# regulated_sensorTHV18.net
KiCad netlist of a schematic drawn in EAGLE
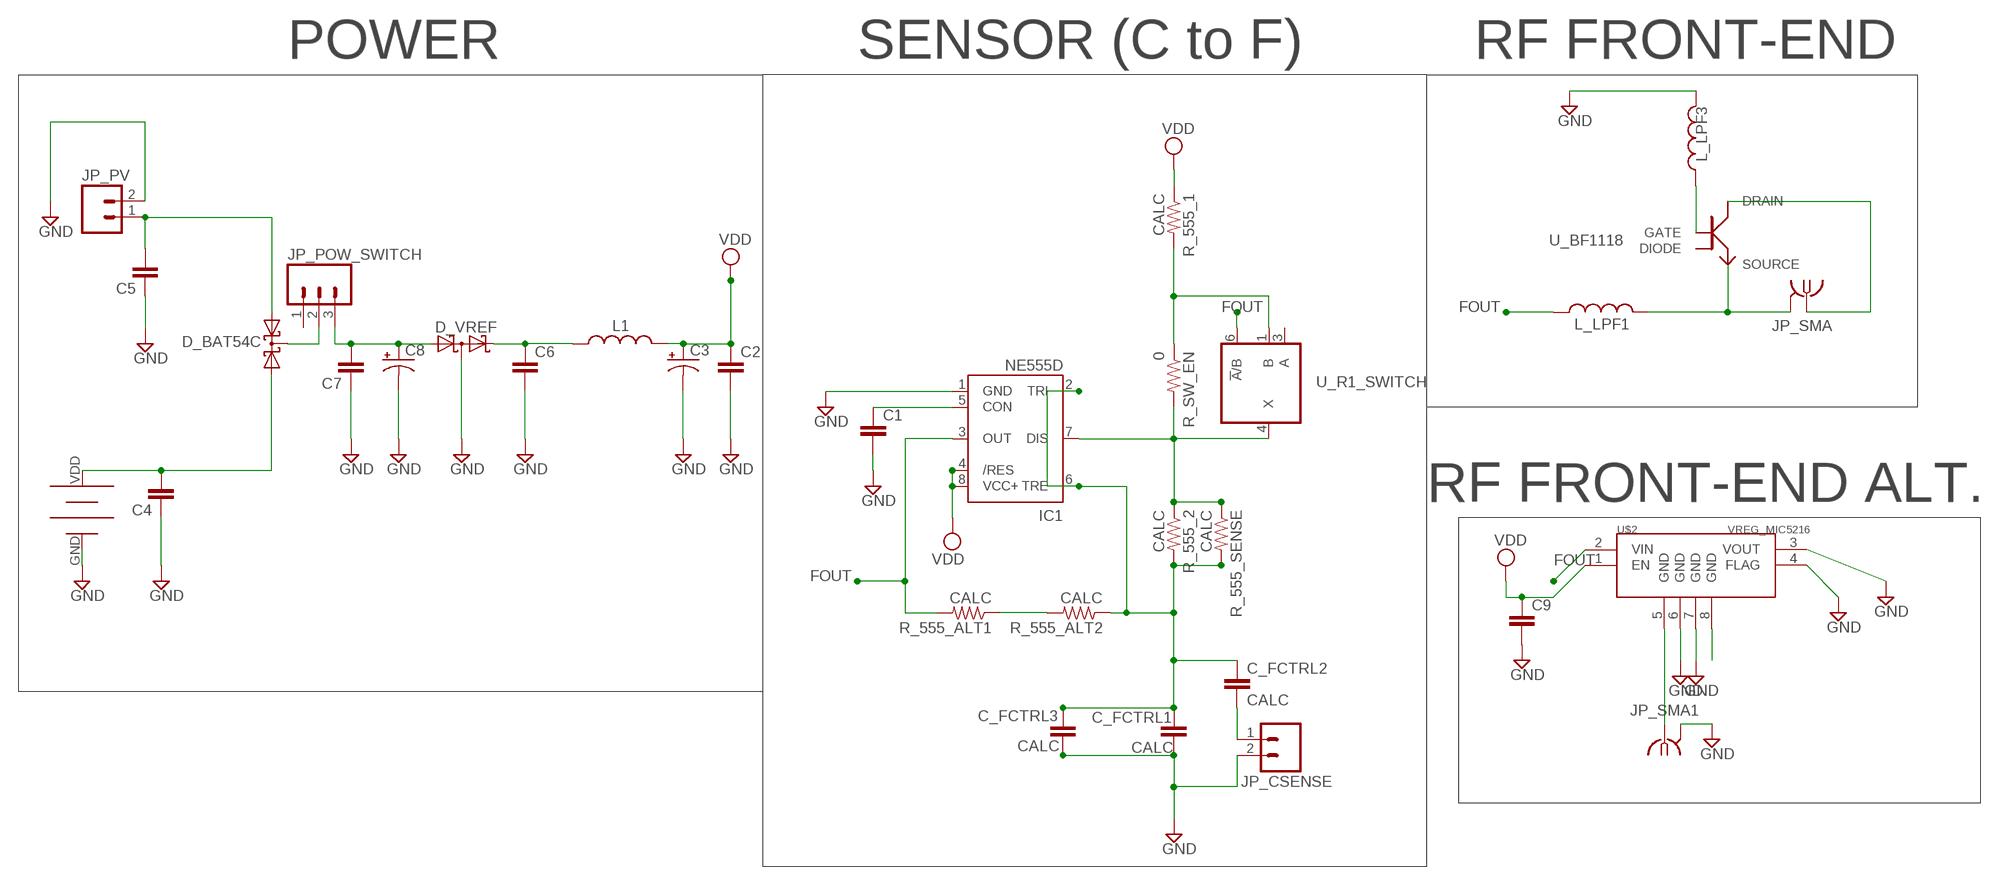
[diagram p0: schematic, sheet 1]

(export (version "E")
  (design (tool "Eeschema 10.0.6"))
  (components
    (comp (ref "C1")
      (value "CAP0603-CAP")
      (footprint "eagle-import:0603-CAP")
      (libsource (lib "eagle-import") (part "CAP0603-CAP"))
    )
    (comp (ref "C2")
      (value "CAP0603-CAP")
      (footprint "eagle-import:0603-CAP")
      (libsource (lib "eagle-import") (part "CAP0603-CAP"))
    )
    (comp (ref "C3")
      (value "CAP_POL1206")
      (footprint "eagle-import:EIA3216")
      (libsource (lib "eagle-import") (part "CAP_POL1206"))
    )
    (comp (ref "C4")
      (value "CAP0603-CAP")
      (footprint "eagle-import:0603-CAP")
      (libsource (lib "eagle-import") (part "CAP0603-CAP"))
    )
    (comp (ref "C5")
      (value "CAP0603-CAP")
      (footprint "eagle-import:0603-CAP")
      (libsource (lib "eagle-import") (part "CAP0603-CAP"))
    )
    (comp (ref "C6")
      (value "CAP0603-CAP")
      (footprint "eagle-import:0603-CAP")
      (libsource (lib "eagle-import") (part "CAP0603-CAP"))
    )
    (comp (ref "C7")
      (value "CAP0603-CAP")
      (footprint "eagle-import:0603-CAP")
      (libsource (lib "eagle-import") (part "CAP0603-CAP"))
    )
    (comp (ref "C8")
      (value "CAP_POL1206")
      (footprint "eagle-import:EIA3216")
      (libsource (lib "eagle-import") (part "CAP_POL1206"))
    )
    (comp (ref "C9")
      (value "CAP0603-CAP")
      (footprint "eagle-import:0603-CAP")
      (libsource (lib "eagle-import") (part "CAP0603-CAP"))
    )
    (comp (ref "C_FCTRL1")
      (value "CALC")
      (footprint "eagle-import:0603-CAP")
      (libsource (lib "eagle-import") (part "CAP0603-CAP"))
    )
    (comp (ref "C_FCTRL2")
      (value "CALC")
      (footprint "eagle-import:0603-CAP")
      (libsource (lib "eagle-import") (part "CAP0603-CAP"))
    )
    (comp (ref "C_FCTRL3")
      (value "CALC")
      (footprint "eagle-import:0603-CAP")
      (libsource (lib "eagle-import") (part "CAP0603-CAP"))
    )
    (comp (ref "D_BAT54C")
      (value "BAT54C")
      (footprint "eagle-import:SOT23")
      (libsource (lib "eagle-import") (part "BAT54C"))
    )
    (comp (ref "D_VREF")
      (value "BAT54S")
      (footprint "eagle-import:SOT23")
      (libsource (lib "eagle-import") (part "BAT54S"))
    )
    (comp (ref "IC1")
      (value "NE555D")
      (footprint "eagle-import:SO08")
      (libsource (lib "eagle-import") (part "NE555D"))
    )
    (comp (ref "JP_CSENSE")
      (value "M02LOCK")
      (footprint "eagle-import:1X02_LOCK")
      (libsource (lib "eagle-import") (part "M02LOCK"))
    )
    (comp (ref "JP_POW_SWITCH")
      (value "M03LOCK")
      (footprint "eagle-import:1X03_LOCK")
      (libsource (lib "eagle-import") (part "M03LOCK"))
    )
    (comp (ref "JP_PV")
      (value "M02LOCK")
      (footprint "eagle-import:1X02_LOCK")
      (libsource (lib "eagle-import") (part "M02LOCK"))
    )
    (comp (ref "JP_SMA")
      (value "SMA-142-0701-881/886")
      (footprint "eagle-import:J502-ND-142-0701-881_886")
      (fields (field (name "MF") "JOHNSON COMPONENTS") (field (name "MPN") "142-0701-881"))
      (libsource (lib "eagle-import") (part "SMA-142-0701-881/886"))
    )
    (comp (ref "JP_SMA1")
      (value "SMA-142-0701-881/886")
      (footprint "eagle-import:J502-ND-142-0701-881_886")
      (fields (field (name "MF") "JOHNSON COMPONENTS") (field (name "MPN") "142-0701-881"))
      (libsource (lib "eagle-import") (part "SMA-142-0701-881/886"))
    )
    (comp (ref "L1")
      (value "INDUCTOR0603")
      (footprint "eagle-import:0603")
      (libsource (lib "eagle-import") (part "INDUCTOR0603"))
    )
    (comp (ref "L_LPF1")
      (value "INDUCTOR0603")
      (footprint "eagle-import:0603")
      (libsource (lib "eagle-import") (part "INDUCTOR0603"))
    )
    (comp (ref "L_LPF3")
      (value "INDUCTOR0603")
      (footprint "eagle-import:0603")
      (libsource (lib "eagle-import") (part "INDUCTOR0603"))
    )
    (comp (ref "R_555_1")
      (value "CALC")
      (footprint "eagle-import:0805")
      (libsource (lib "eagle-import") (part "RESISTOR0805-RES"))
    )
    (comp (ref "R_555_2")
      (value "CALC")
      (footprint "eagle-import:0603-RES")
      (libsource (lib "eagle-import") (part "RESISTOR0603-RES"))
    )
    (comp (ref "R_555_ALT1")
      (value "CALC")
      (footprint "eagle-import:0603-RES")
      (libsource (lib "eagle-import") (part "RESISTOR0603-RES"))
    )
    (comp (ref "R_555_ALT2")
      (value "CALC")
      (footprint "eagle-import:0603-RES")
      (libsource (lib "eagle-import") (part "RESISTOR0603-RES"))
    )
    (comp (ref "R_555_SENSE")
      (value "CALC")
      (footprint "eagle-import:0603-RES")
      (libsource (lib "eagle-import") (part "RESISTOR0603-RES"))
    )
    (comp (ref "R_SW_EN")
      (value "0")
      (footprint "eagle-import:0805")
      (libsource (lib "eagle-import") (part "RESISTOR0805-RES"))
    )
    (comp (ref "U$1")
      (value "BATTERY_AAA_EAGLE_PLASTIC_DEVICES_DOUBLE")
      (footprint "eagle-import:BATTERY-AAA-50MM-DOUBLE")
      (libsource (lib "eagle-import") (part "BATTERY_AAA_EAGLE_PLASTIC_DEVICES_DOUBLE"))
    )
    (comp (ref "U$2")
      (value "VREG_MIC5216")
      (footprint "eagle-import:MSOP8")
      (libsource (lib "eagle-import") (part "VREG_MIC5216"))
    )
    (comp (ref "U_BF1118")
      (value "BF1118SOT343R_NXP")
      (footprint "eagle-import:SOT343R")
      (libsource (lib "eagle-import") (part "BF1118SOT343R_NXP"))
    )
    (comp (ref "U_R1_SWITCH")
      (value "741G3157DCKR")
      (footprint "eagle-import:DCK_R-PDSO-G6")
      (libsource (lib "eagle-import") (part "741G3157DCKR"))
    )
  )
  (nets
    (net (code "1") (name "/FOUT") (class "Default")
      (node (ref "IC1") (pin "3") (pinfunction "OUT_3") (pintype "output"))
      (node (ref "L_LPF1") (pin "1") (pinfunction "1_1") (pintype "passive"))
      (node (ref "R_555_ALT1") (pin "2") (pinfunction "2_2") (pintype "passive"))
      (node (ref "U$2") (pin "2") (pinfunction "VIN_2") (pintype "bidirectional"))
      (node (ref "U_R1_SWITCH") (pin "6") (pinfunction "~{A}/B_6") (pintype "input"))
    )
    (net (code "2") (name "GND") (class "Default")
      (node (ref "C1") (pin "2") (pinfunction "2_2") (pintype "passive"))
      (node (ref "C2") (pin "2") (pinfunction "2_2") (pintype "passive"))
      (node (ref "C3") (pin "C") (pinfunction "-_C") (pintype "passive"))
      (node (ref "C4") (pin "1") (pinfunction "1_1") (pintype "passive"))
      (node (ref "C5") (pin "1") (pinfunction "1_1") (pintype "passive"))
      (node (ref "C6") (pin "2") (pinfunction "2_2") (pintype "passive"))
      (node (ref "C7") (pin "1") (pinfunction "1_1") (pintype "passive"))
      (node (ref "C8") (pin "C") (pinfunction "-_C") (pintype "passive"))
      (node (ref "C9") (pin "2") (pinfunction "2_2") (pintype "passive"))
      (node (ref "C_FCTRL1") (pin "2") (pinfunction "2_2") (pintype "passive"))
      (node (ref "C_FCTRL3") (pin "2") (pinfunction "2_2") (pintype "passive"))
      (node (ref "D_VREF") (pin "3") (pinfunction "C1A2_3") (pintype "passive"))
      (node (ref "IC1") (pin "1") (pinfunction "GND_1") (pintype "power_in"))
      (node (ref "JP_CSENSE") (pin "2") (pinfunction "2_2") (pintype "passive"))
      (node (ref "JP_PV") (pin "2") (pinfunction "2_2") (pintype "passive"))
      (node (ref "JP_SMA1") (pin "G@1") (pinfunction "2_G@1") (pintype "passive"))
      (node (ref "JP_SMA1") (pin "G@2") (pinfunction "2_G@2") (pintype "passive"))
      (node (ref "JP_SMA1") (pin "G@3") (pinfunction "2_G@3") (pintype "passive"))
      (node (ref "JP_SMA1") (pin "G@4") (pinfunction "2_G@4") (pintype "passive"))
      (node (ref "L_LPF3") (pin "2") (pinfunction "2_2") (pintype "passive"))
      (node (ref "U$1") (pin "GND") (pinfunction "GND_GND") (pintype "bidirectional"))
      (node (ref "U$2") (pin "3") (pinfunction "VOUT_3") (pintype "bidirectional"))
      (node (ref "U$2") (pin "4") (pinfunction "FLAG_4") (pintype "bidirectional"))
      (node (ref "U$2") (pin "6") (pinfunction "GND_6") (pintype "bidirectional"))
      (node (ref "U$2") (pin "7") (pinfunction "GND_7") (pintype "bidirectional"))
    )
    (net (code "3") (name "Net-(C8-+)") (class "Default")
      (node (ref "C7") (pin "2") (pinfunction "2_2") (pintype "passive"))
      (node (ref "C8") (pin "A") (pinfunction "+_A") (pintype "passive"))
      (node (ref "D_VREF") (pin "1") (pinfunction "A1_1") (pintype "passive"))
      (node (ref "JP_POW_SWITCH") (pin "3") (pinfunction "3_3") (pintype "passive"))
    )
    (net (code "4") (name "Net-(C_FCTRL2-Pad2)") (class "Default")
      (node (ref "C_FCTRL2") (pin "2") (pinfunction "2_2") (pintype "passive"))
      (node (ref "JP_CSENSE") (pin "1") (pinfunction "1_1") (pintype "passive"))
    )
    (net (code "5") (name "Net-(D_BAT54C-A1)") (class "Default")
      (node (ref "C5") (pin "2") (pinfunction "2_2") (pintype "passive"))
      (node (ref "D_BAT54C") (pin "1") (pinfunction "A1_1") (pintype "passive"))
      (node (ref "JP_PV") (pin "1") (pinfunction "1_1") (pintype "passive"))
    )
    (net (code "6") (name "Net-(D_BAT54C-A2)") (class "Default")
      (node (ref "C4") (pin "2") (pinfunction "2_2") (pintype "passive"))
      (node (ref "D_BAT54C") (pin "2") (pinfunction "A2_2") (pintype "passive"))
      (node (ref "U$1") (pin "VDD") (pinfunction "VDD_VDD") (pintype "bidirectional"))
    )
    (net (code "7") (name "Net-(D_BAT54C-CC)") (class "Default")
      (node (ref "D_BAT54C") (pin "3") (pinfunction "CC_3") (pintype "passive"))
      (node (ref "JP_POW_SWITCH") (pin "2") (pinfunction "2_2") (pintype "passive"))
    )
    (net (code "8") (name "Net-(D_VREF-C2)") (class "Default")
      (node (ref "C6") (pin "1") (pinfunction "1_1") (pintype "passive"))
      (node (ref "D_VREF") (pin "2") (pinfunction "C2_2") (pintype "passive"))
      (node (ref "L1") (pin "1") (pinfunction "1_1") (pintype "passive"))
    )
    (net (code "9") (name "Net-(IC1-CON)") (class "Default")
      (node (ref "C1") (pin "1") (pinfunction "1_1") (pintype "passive"))
      (node (ref "IC1") (pin "5") (pinfunction "CON_5") (pintype "input"))
    )
    (net (code "10") (name "Net-(IC1-DIS)") (class "Default")
      (node (ref "IC1") (pin "7") (pinfunction "DIS_7") (pintype "input"))
      (node (ref "R_555_2") (pin "1") (pinfunction "1_1") (pintype "passive"))
      (node (ref "R_555_SENSE") (pin "1") (pinfunction "1_1") (pintype "passive"))
      (node (ref "R_SW_EN") (pin "2") (pinfunction "2_2") (pintype "passive"))
      (node (ref "U_R1_SWITCH") (pin "4") (pinfunction "X_4") (pintype "bidirectional"))
    )
    (net (code "11") (name "Net-(IC1-TRE)") (class "Default")
      (node (ref "C_FCTRL1") (pin "1") (pinfunction "1_1") (pintype "passive"))
      (node (ref "C_FCTRL2") (pin "1") (pinfunction "1_1") (pintype "passive"))
      (node (ref "C_FCTRL3") (pin "1") (pinfunction "1_1") (pintype "passive"))
      (node (ref "IC1") (pin "2") (pinfunction "TRI_2") (pintype "input"))
      (node (ref "IC1") (pin "6") (pinfunction "TRE_6") (pintype "input"))
      (node (ref "R_555_2") (pin "2") (pinfunction "2_2") (pintype "passive"))
      (node (ref "R_555_ALT2") (pin "1") (pinfunction "1_1") (pintype "passive"))
      (node (ref "R_555_SENSE") (pin "2") (pinfunction "2_2") (pintype "passive"))
    )
    (net (code "12") (name "Net-(JP_SMA1-Pad1)") (class "Default")
      (node (ref "JP_SMA1") (pin "1") (pinfunction "1_1") (pintype "passive"))
      (node (ref "U$2") (pin "5") (pinfunction "GND_5") (pintype "bidirectional"))
    )
    (net (code "13") (name "Net-(R_555_ALT1-Pad1)") (class "Default")
      (node (ref "R_555_ALT1") (pin "1") (pinfunction "1_1") (pintype "passive"))
      (node (ref "R_555_ALT2") (pin "2") (pinfunction "2_2") (pintype "passive"))
    )
    (net (code "14") (name "Net-(U_BF1118-DRAIN)") (class "Default")
      (node (ref "JP_SMA") (pin "1") (pinfunction "1_1") (pintype "passive"))
      (node (ref "U_BF1118") (pin "4") (pinfunction "DRAIN_4") (pintype "bidirectional"))
    )
    (net (code "15") (name "Net-(U_BF1118-GATE)") (class "Default")
      (node (ref "L_LPF3") (pin "1") (pinfunction "1_1") (pintype "passive"))
      (node (ref "U_BF1118") (pin "1") (pinfunction "GATE_1") (pintype "bidirectional"))
    )
    (net (code "16") (name "Net-(U_BF1118-SOURCE)") (class "Default")
      (node (ref "JP_SMA") (pin "G@1") (pinfunction "2_G@1") (pintype "passive"))
      (node (ref "JP_SMA") (pin "G@2") (pinfunction "2_G@2") (pintype "passive"))
      (node (ref "JP_SMA") (pin "G@3") (pinfunction "2_G@3") (pintype "passive"))
      (node (ref "JP_SMA") (pin "G@4") (pinfunction "2_G@4") (pintype "passive"))
      (node (ref "L_LPF1") (pin "2") (pinfunction "2_2") (pintype "passive"))
      (node (ref "U_BF1118") (pin "3") (pinfunction "SOURCE_3") (pintype "bidirectional"))
    )
    (net (code "17") (name "Net-(U_R1_SWITCHA-B)") (class "Default")
      (node (ref "R_555_1") (pin "2") (pinfunction "2_2") (pintype "passive"))
      (node (ref "R_SW_EN") (pin "1") (pinfunction "1_1") (pintype "passive"))
      (node (ref "U_R1_SWITCH") (pin "1") (pinfunction "B_1") (pintype "bidirectional"))
    )
    (net (code "18") (name "VDD") (class "Default")
      (node (ref "C2") (pin "1") (pinfunction "1_1") (pintype "passive"))
      (node (ref "C3") (pin "A") (pinfunction "+_A") (pintype "passive"))
      (node (ref "C9") (pin "1") (pinfunction "1_1") (pintype "passive"))
      (node (ref "IC1") (pin "4") (pinfunction "/RES_4") (pintype "input"))
      (node (ref "IC1") (pin "8") (pinfunction "VCC+_8") (pintype "power_in"))
      (node (ref "L1") (pin "2") (pinfunction "2_2") (pintype "passive"))
      (node (ref "R_555_1") (pin "1") (pinfunction "1_1") (pintype "passive"))
      (node (ref "U$2") (pin "1") (pinfunction "EN_1") (pintype "bidirectional"))
    )
    (net (code "19") (name "unconnected-(JP_POW_SWITCH-Pad1)") (class "Default")
      (node (ref "JP_POW_SWITCH") (pin "1") (pinfunction "1_1") (pintype "passive"))
    )
    (net (code "20") (name "unconnected-(U$2-GND-Pad8)") (class "Default")
      (node (ref "U$2") (pin "8") (pinfunction "GND_8") (pintype "bidirectional"))
    )
    (net (code "21") (name "unconnected-(U_BF1118-DIODE-Pad2)") (class "Default")
      (node (ref "U_BF1118") (pin "2") (pinfunction "DIODE_2") (pintype "bidirectional"))
    )
    (net (code "22") (name "unconnected-(U_R1_SWITCHA-A-Pad3)") (class "Default")
      (node (ref "U_R1_SWITCH") (pin "3") (pinfunction "A_3") (pintype "bidirectional"))
    )
  )
)
